# 05_ALU_OUT.net
KiCad netlist of a schematic drawn in EAGLE
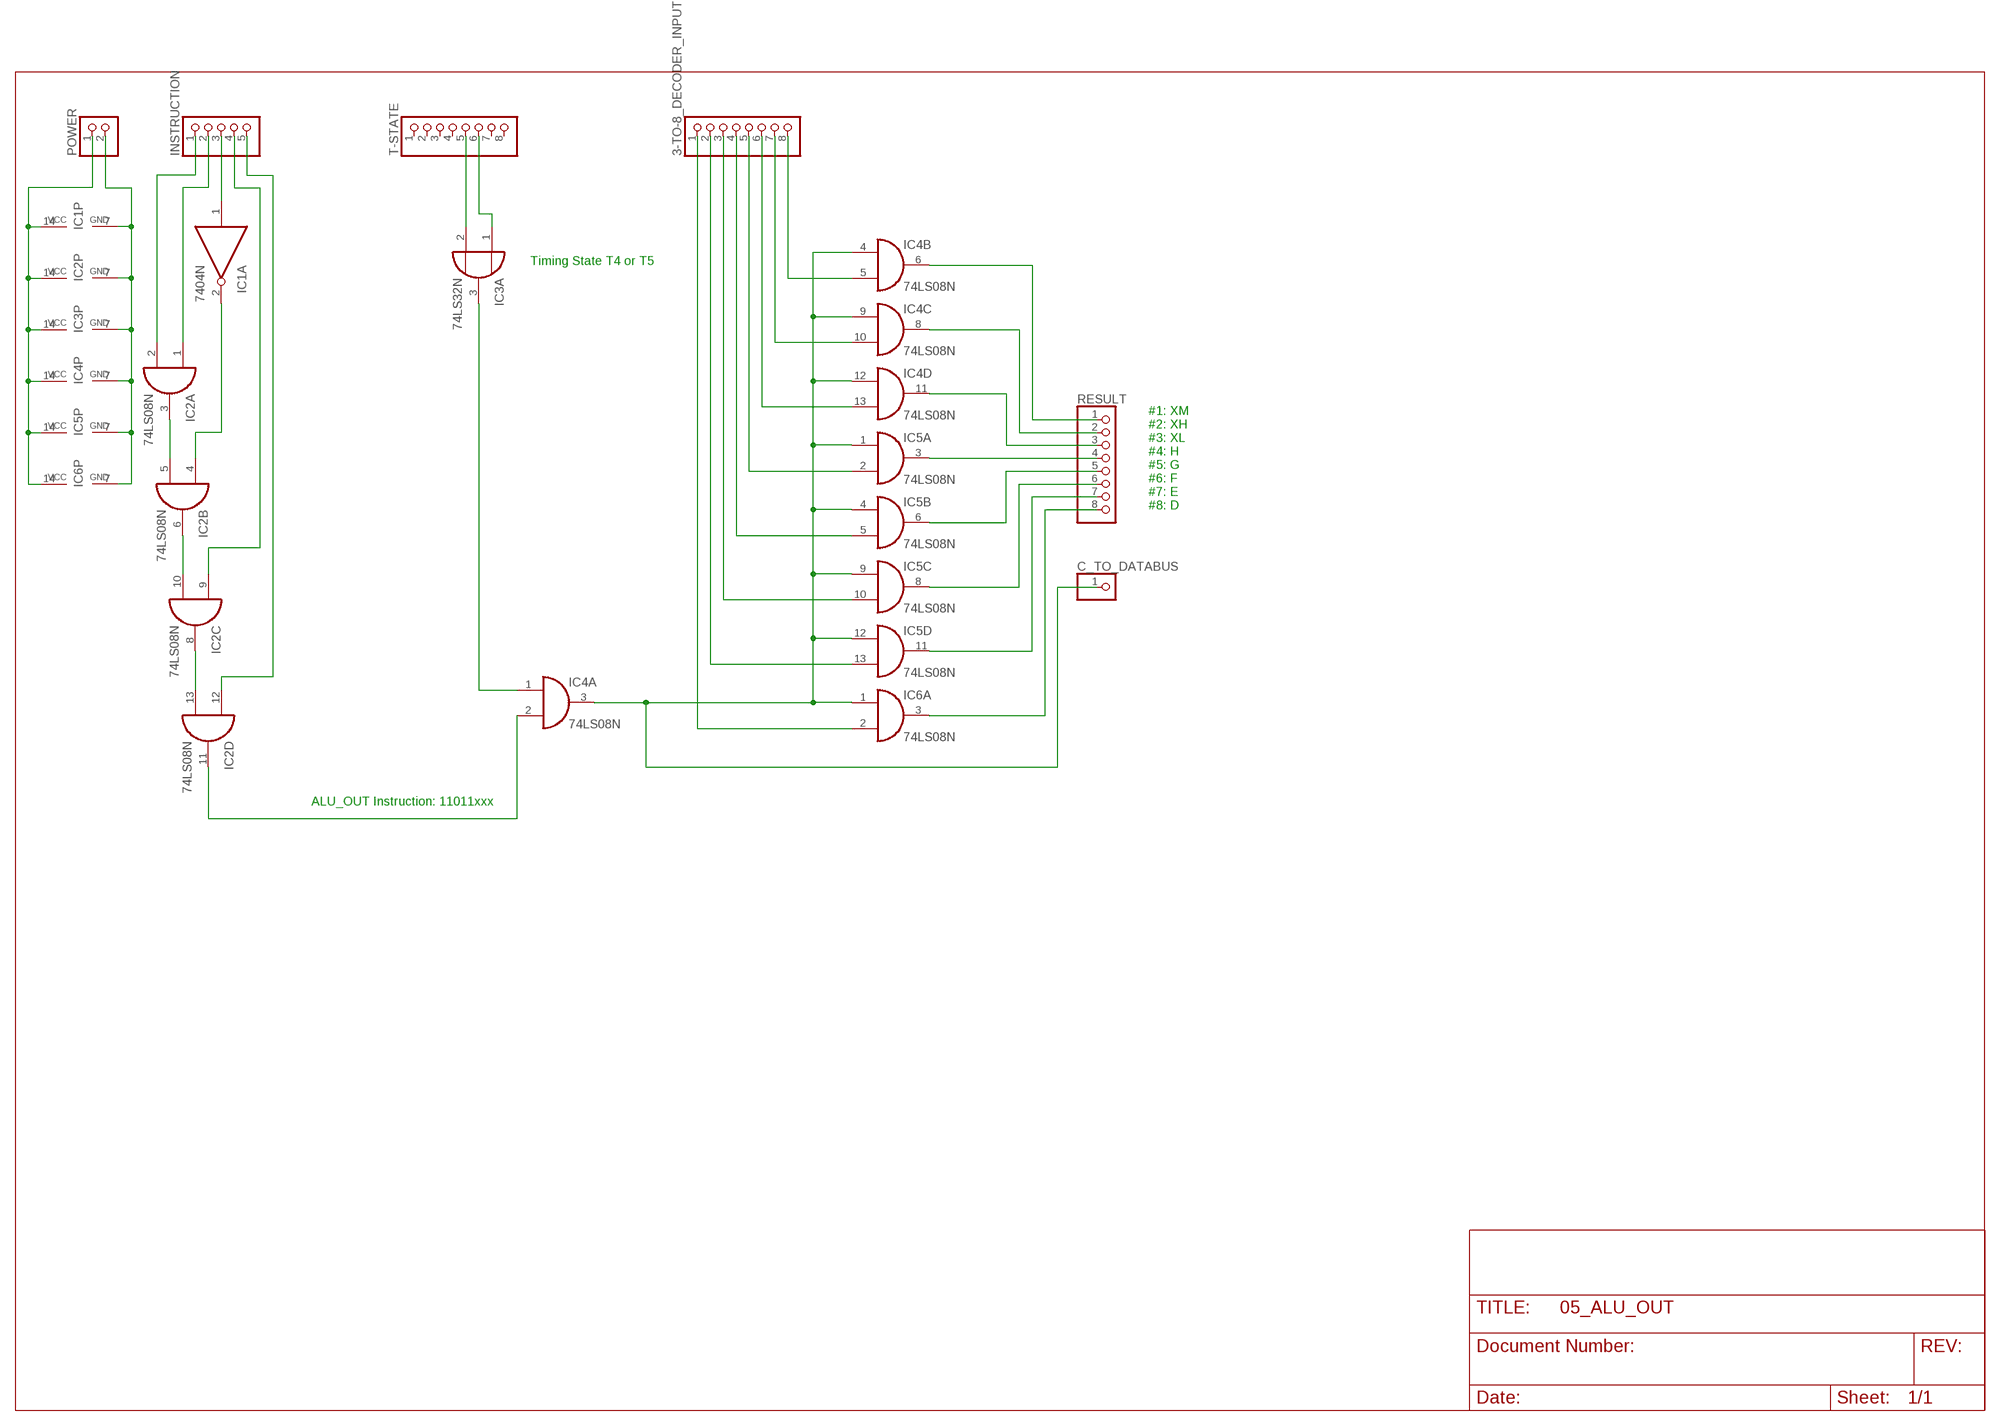
[diagram p0: schematic, sheet 1]

(export (version "E")
  (design (tool "Eeschema 10.0.6"))
  (components
    (comp (ref "3-TO-8_DECODER_INPUT")
      (value "PINHD-1X8")
      (footprint "eagle-import:1X08")
      (libsource (lib "eagle-import") (part "PINHD-1X8"))
    )
    (comp (ref "C_TO_DATABUS")
      (value "PINHD-1X1")
      (footprint "eagle-import:1X01")
      (libsource (lib "eagle-import") (part "PINHD-1X1"))
    )
    (comp (ref "IC1")
      (value "7404N")
      (footprint "eagle-import:DIL14")
      (libsource (lib "eagle-import") (part "7404N"))
    )
    (comp (ref "IC2")
      (value "74LS08N")
      (footprint "eagle-import:DIL14")
      (libsource (lib "eagle-import") (part "7408NLS"))
    )
    (comp (ref "IC3")
      (value "74LS32N")
      (footprint "eagle-import:DIL14")
      (libsource (lib "eagle-import") (part "7432NLS"))
    )
    (comp (ref "IC4")
      (value "74LS08N")
      (footprint "eagle-import:DIL14")
      (libsource (lib "eagle-import") (part "7408NLS"))
    )
    (comp (ref "IC5")
      (value "74LS08N")
      (footprint "eagle-import:DIL14")
      (libsource (lib "eagle-import") (part "7408NLS"))
    )
    (comp (ref "IC6")
      (value "74LS08N")
      (footprint "eagle-import:DIL14")
      (libsource (lib "eagle-import") (part "7408NLS"))
    )
    (comp (ref "INSTRUCTION")
      (value "PINHD-1X5")
      (footprint "eagle-import:1X05")
      (libsource (lib "eagle-import") (part "PINHD-1X5"))
    )
    (comp (ref "POWER")
      (value "PINHD-1X2")
      (footprint "eagle-import:1X02")
      (libsource (lib "eagle-import") (part "PINHD-1X2"))
    )
    (comp (ref "RESULT")
      (value "PINHD-1X8")
      (footprint "eagle-import:1X08")
      (libsource (lib "eagle-import") (part "PINHD-1X8"))
    )
    (comp (ref "T-STATE")
      (value "PINHD-1X8")
      (footprint "eagle-import:1X08")
      (libsource (lib "eagle-import") (part "PINHD-1X8"))
    )
  )
  (nets
    (net (code "1") (name "Net-(IC1A-I)") (class "Default")
      (node (ref "IC1") (pin "1") (pinfunction "I_1") (pintype "input"))
      (node (ref "INSTRUCTION") (pin "3") (pinfunction "3_3") (pintype "passive"))
    )
    (net (code "2") (name "Net-(IC1A-O)") (class "Default")
      (node (ref "IC1") (pin "2") (pinfunction "O_2") (pintype "output"))
      (node (ref "IC2") (pin "4") (pinfunction "I0_4") (pintype "input"))
    )
    (net (code "3") (name "Net-(IC1G-GND)") (class "Default")
      (node (ref "IC1") (pin "7") (pinfunction "GND_7") (pintype "power_in"))
      (node (ref "IC2") (pin "7") (pinfunction "GND_7") (pintype "power_in"))
      (node (ref "IC3") (pin "7") (pinfunction "GND_7") (pintype "power_in"))
      (node (ref "IC4") (pin "7") (pinfunction "GND_7") (pintype "power_in"))
      (node (ref "IC5") (pin "7") (pinfunction "GND_7") (pintype "power_in"))
      (node (ref "IC6") (pin "7") (pinfunction "GND_7") (pintype "power_in"))
      (node (ref "POWER") (pin "2") (pinfunction "2_2") (pintype "passive"))
    )
    (net (code "4") (name "Net-(IC1G-VCC)") (class "Default")
      (node (ref "IC1") (pin "14") (pinfunction "VCC_14") (pintype "power_in"))
      (node (ref "IC2") (pin "14") (pinfunction "VCC_14") (pintype "power_in"))
      (node (ref "IC3") (pin "14") (pinfunction "VCC_14") (pintype "power_in"))
      (node (ref "IC4") (pin "14") (pinfunction "VCC_14") (pintype "power_in"))
      (node (ref "IC5") (pin "14") (pinfunction "VCC_14") (pintype "power_in"))
      (node (ref "IC6") (pin "14") (pinfunction "VCC_14") (pintype "power_in"))
      (node (ref "POWER") (pin "1") (pinfunction "1_1") (pintype "passive"))
    )
    (net (code "5") (name "Net-(IC2A-I0)") (class "Default")
      (node (ref "IC2") (pin "1") (pinfunction "I0_1") (pintype "input"))
      (node (ref "INSTRUCTION") (pin "2") (pinfunction "2_2") (pintype "passive"))
    )
    (net (code "6") (name "Net-(IC2A-I1)") (class "Default")
      (node (ref "IC2") (pin "2") (pinfunction "I1_2") (pintype "input"))
      (node (ref "INSTRUCTION") (pin "1") (pinfunction "1_1") (pintype "passive"))
    )
    (net (code "7") (name "Net-(IC2A-O)") (class "Default")
      (node (ref "IC2") (pin "3") (pinfunction "O_3") (pintype "output"))
      (node (ref "IC2") (pin "5") (pinfunction "I1_5") (pintype "input"))
    )
    (net (code "8") (name "Net-(IC2B-O)") (class "Default")
      (node (ref "IC2") (pin "10") (pinfunction "I1_10") (pintype "input"))
      (node (ref "IC2") (pin "6") (pinfunction "O_6") (pintype "output"))
    )
    (net (code "9") (name "Net-(IC2C-I0)") (class "Default")
      (node (ref "IC2") (pin "9") (pinfunction "I0_9") (pintype "input"))
      (node (ref "INSTRUCTION") (pin "4") (pinfunction "4_4") (pintype "passive"))
    )
    (net (code "10") (name "Net-(IC2C-O)") (class "Default")
      (node (ref "IC2") (pin "13") (pinfunction "I1_13") (pintype "input"))
      (node (ref "IC2") (pin "8") (pinfunction "O_8") (pintype "output"))
    )
    (net (code "11") (name "Net-(IC2D-I0)") (class "Default")
      (node (ref "IC2") (pin "12") (pinfunction "I0_12") (pintype "input"))
      (node (ref "INSTRUCTION") (pin "5") (pinfunction "5_5") (pintype "passive"))
    )
    (net (code "12") (name "Net-(IC2D-O)") (class "Default")
      (node (ref "IC2") (pin "11") (pinfunction "O_11") (pintype "output"))
      (node (ref "IC4") (pin "2") (pinfunction "I1_2") (pintype "input"))
    )
    (net (code "13") (name "Net-(IC3A-I0)") (class "Default")
      (node (ref "IC3") (pin "1") (pinfunction "I0_1") (pintype "input"))
      (node (ref "T-STATE") (pin "6") (pinfunction "6_6") (pintype "passive"))
    )
    (net (code "14") (name "Net-(IC3A-I1)") (class "Default")
      (node (ref "IC3") (pin "2") (pinfunction "I1_2") (pintype "input"))
      (node (ref "T-STATE") (pin "5") (pinfunction "5_5") (pintype "passive"))
    )
    (net (code "15") (name "Net-(IC3A-O)") (class "Default")
      (node (ref "IC3") (pin "3") (pinfunction "O_3") (pintype "output"))
      (node (ref "IC4") (pin "1") (pinfunction "I0_1") (pintype "input"))
    )
    (net (code "16") (name "Net-(IC4A-O)") (class "Default")
      (node (ref "C_TO_DATABUS") (pin "1") (pinfunction "1_1") (pintype "passive"))
      (node (ref "IC4") (pin "12") (pinfunction "I0_12") (pintype "input"))
      (node (ref "IC4") (pin "3") (pinfunction "O_3") (pintype "output"))
      (node (ref "IC4") (pin "4") (pinfunction "I0_4") (pintype "input"))
      (node (ref "IC4") (pin "9") (pinfunction "I0_9") (pintype "input"))
      (node (ref "IC5") (pin "1") (pinfunction "I0_1") (pintype "input"))
      (node (ref "IC5") (pin "12") (pinfunction "I0_12") (pintype "input"))
      (node (ref "IC5") (pin "4") (pinfunction "I0_4") (pintype "input"))
      (node (ref "IC5") (pin "9") (pinfunction "I0_9") (pintype "input"))
      (node (ref "IC6") (pin "1") (pinfunction "I0_1") (pintype "input"))
    )
    (net (code "17") (name "Net-(IC4B-I1)") (class "Default")
      (node (ref "3-TO-8_DECODER_INPUT") (pin "8") (pinfunction "8_8") (pintype "passive"))
      (node (ref "IC4") (pin "5") (pinfunction "I1_5") (pintype "input"))
    )
    (net (code "18") (name "Net-(IC4B-O)") (class "Default")
      (node (ref "IC4") (pin "6") (pinfunction "O_6") (pintype "output"))
      (node (ref "RESULT") (pin "1") (pinfunction "1_1") (pintype "passive"))
    )
    (net (code "19") (name "Net-(IC4C-I1)") (class "Default")
      (node (ref "3-TO-8_DECODER_INPUT") (pin "7") (pinfunction "7_7") (pintype "passive"))
      (node (ref "IC4") (pin "10") (pinfunction "I1_10") (pintype "input"))
    )
    (net (code "20") (name "Net-(IC4C-O)") (class "Default")
      (node (ref "IC4") (pin "8") (pinfunction "O_8") (pintype "output"))
      (node (ref "RESULT") (pin "2") (pinfunction "2_2") (pintype "passive"))
    )
    (net (code "21") (name "Net-(IC4D-I1)") (class "Default")
      (node (ref "3-TO-8_DECODER_INPUT") (pin "6") (pinfunction "6_6") (pintype "passive"))
      (node (ref "IC4") (pin "13") (pinfunction "I1_13") (pintype "input"))
    )
    (net (code "22") (name "Net-(IC4D-O)") (class "Default")
      (node (ref "IC4") (pin "11") (pinfunction "O_11") (pintype "output"))
      (node (ref "RESULT") (pin "3") (pinfunction "3_3") (pintype "passive"))
    )
    (net (code "23") (name "Net-(IC5A-I1)") (class "Default")
      (node (ref "3-TO-8_DECODER_INPUT") (pin "5") (pinfunction "5_5") (pintype "passive"))
      (node (ref "IC5") (pin "2") (pinfunction "I1_2") (pintype "input"))
    )
    (net (code "24") (name "Net-(IC5A-O)") (class "Default")
      (node (ref "IC5") (pin "3") (pinfunction "O_3") (pintype "output"))
      (node (ref "RESULT") (pin "4") (pinfunction "4_4") (pintype "passive"))
    )
    (net (code "25") (name "Net-(IC5B-I1)") (class "Default")
      (node (ref "3-TO-8_DECODER_INPUT") (pin "4") (pinfunction "4_4") (pintype "passive"))
      (node (ref "IC5") (pin "5") (pinfunction "I1_5") (pintype "input"))
    )
    (net (code "26") (name "Net-(IC5B-O)") (class "Default")
      (node (ref "IC5") (pin "6") (pinfunction "O_6") (pintype "output"))
      (node (ref "RESULT") (pin "5") (pinfunction "5_5") (pintype "passive"))
    )
    (net (code "27") (name "Net-(IC5C-I1)") (class "Default")
      (node (ref "3-TO-8_DECODER_INPUT") (pin "3") (pinfunction "3_3") (pintype "passive"))
      (node (ref "IC5") (pin "10") (pinfunction "I1_10") (pintype "input"))
    )
    (net (code "28") (name "Net-(IC5C-O)") (class "Default")
      (node (ref "IC5") (pin "8") (pinfunction "O_8") (pintype "output"))
      (node (ref "RESULT") (pin "6") (pinfunction "6_6") (pintype "passive"))
    )
    (net (code "29") (name "Net-(IC5D-I1)") (class "Default")
      (node (ref "3-TO-8_DECODER_INPUT") (pin "2") (pinfunction "2_2") (pintype "passive"))
      (node (ref "IC5") (pin "13") (pinfunction "I1_13") (pintype "input"))
    )
    (net (code "30") (name "Net-(IC5D-O)") (class "Default")
      (node (ref "IC5") (pin "11") (pinfunction "O_11") (pintype "output"))
      (node (ref "RESULT") (pin "7") (pinfunction "7_7") (pintype "passive"))
    )
    (net (code "31") (name "Net-(IC6A-I1)") (class "Default")
      (node (ref "3-TO-8_DECODER_INPUT") (pin "1") (pinfunction "1_1") (pintype "passive"))
      (node (ref "IC6") (pin "2") (pinfunction "I1_2") (pintype "input"))
    )
    (net (code "32") (name "Net-(IC6A-O)") (class "Default")
      (node (ref "IC6") (pin "3") (pinfunction "O_3") (pintype "output"))
      (node (ref "RESULT") (pin "8") (pinfunction "8_8") (pintype "passive"))
    )
    (net (code "33") (name "unconnected-(T-STATE-Pad1)") (class "Default")
      (node (ref "T-STATE") (pin "1") (pinfunction "1_1") (pintype "passive"))
    )
    (net (code "34") (name "unconnected-(T-STATE-Pad2)") (class "Default")
      (node (ref "T-STATE") (pin "2") (pinfunction "2_2") (pintype "passive"))
    )
    (net (code "35") (name "unconnected-(T-STATE-Pad3)") (class "Default")
      (node (ref "T-STATE") (pin "3") (pinfunction "3_3") (pintype "passive"))
    )
    (net (code "36") (name "unconnected-(T-STATE-Pad4)") (class "Default")
      (node (ref "T-STATE") (pin "4") (pinfunction "4_4") (pintype "passive"))
    )
    (net (code "37") (name "unconnected-(T-STATE-Pad7)") (class "Default")
      (node (ref "T-STATE") (pin "7") (pinfunction "7_7") (pintype "passive"))
    )
    (net (code "38") (name "unconnected-(T-STATE-Pad8)") (class "Default")
      (node (ref "T-STATE") (pin "8") (pinfunction "8_8") (pintype "passive"))
    )
  )
)
